# M701D.net
KiCad netlist of a schematic drawn in EAGLE
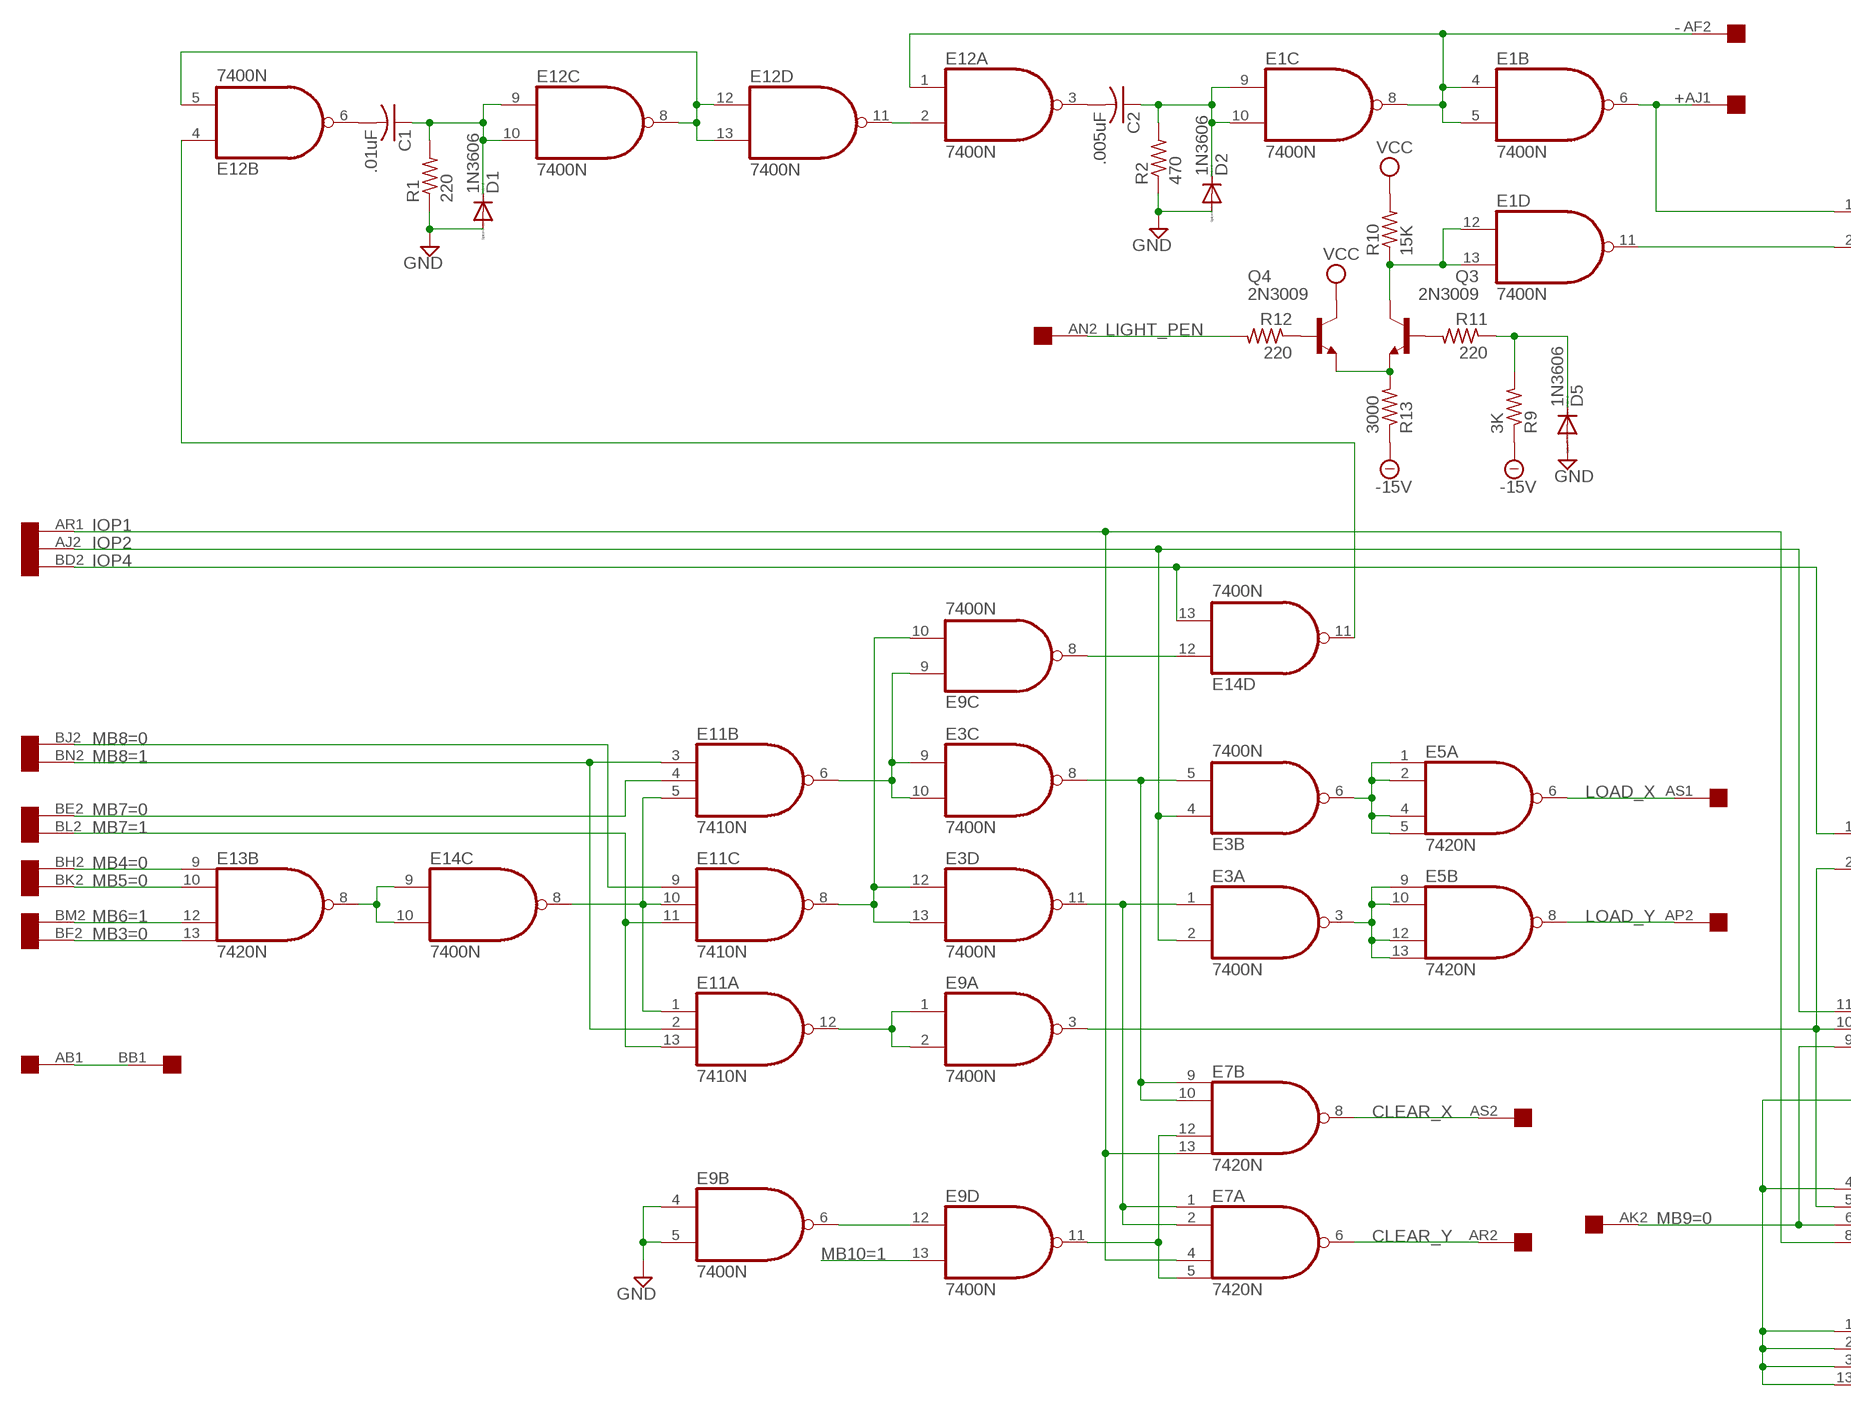
[diagram p0: schematic, sheet 1, part 1 of 2]
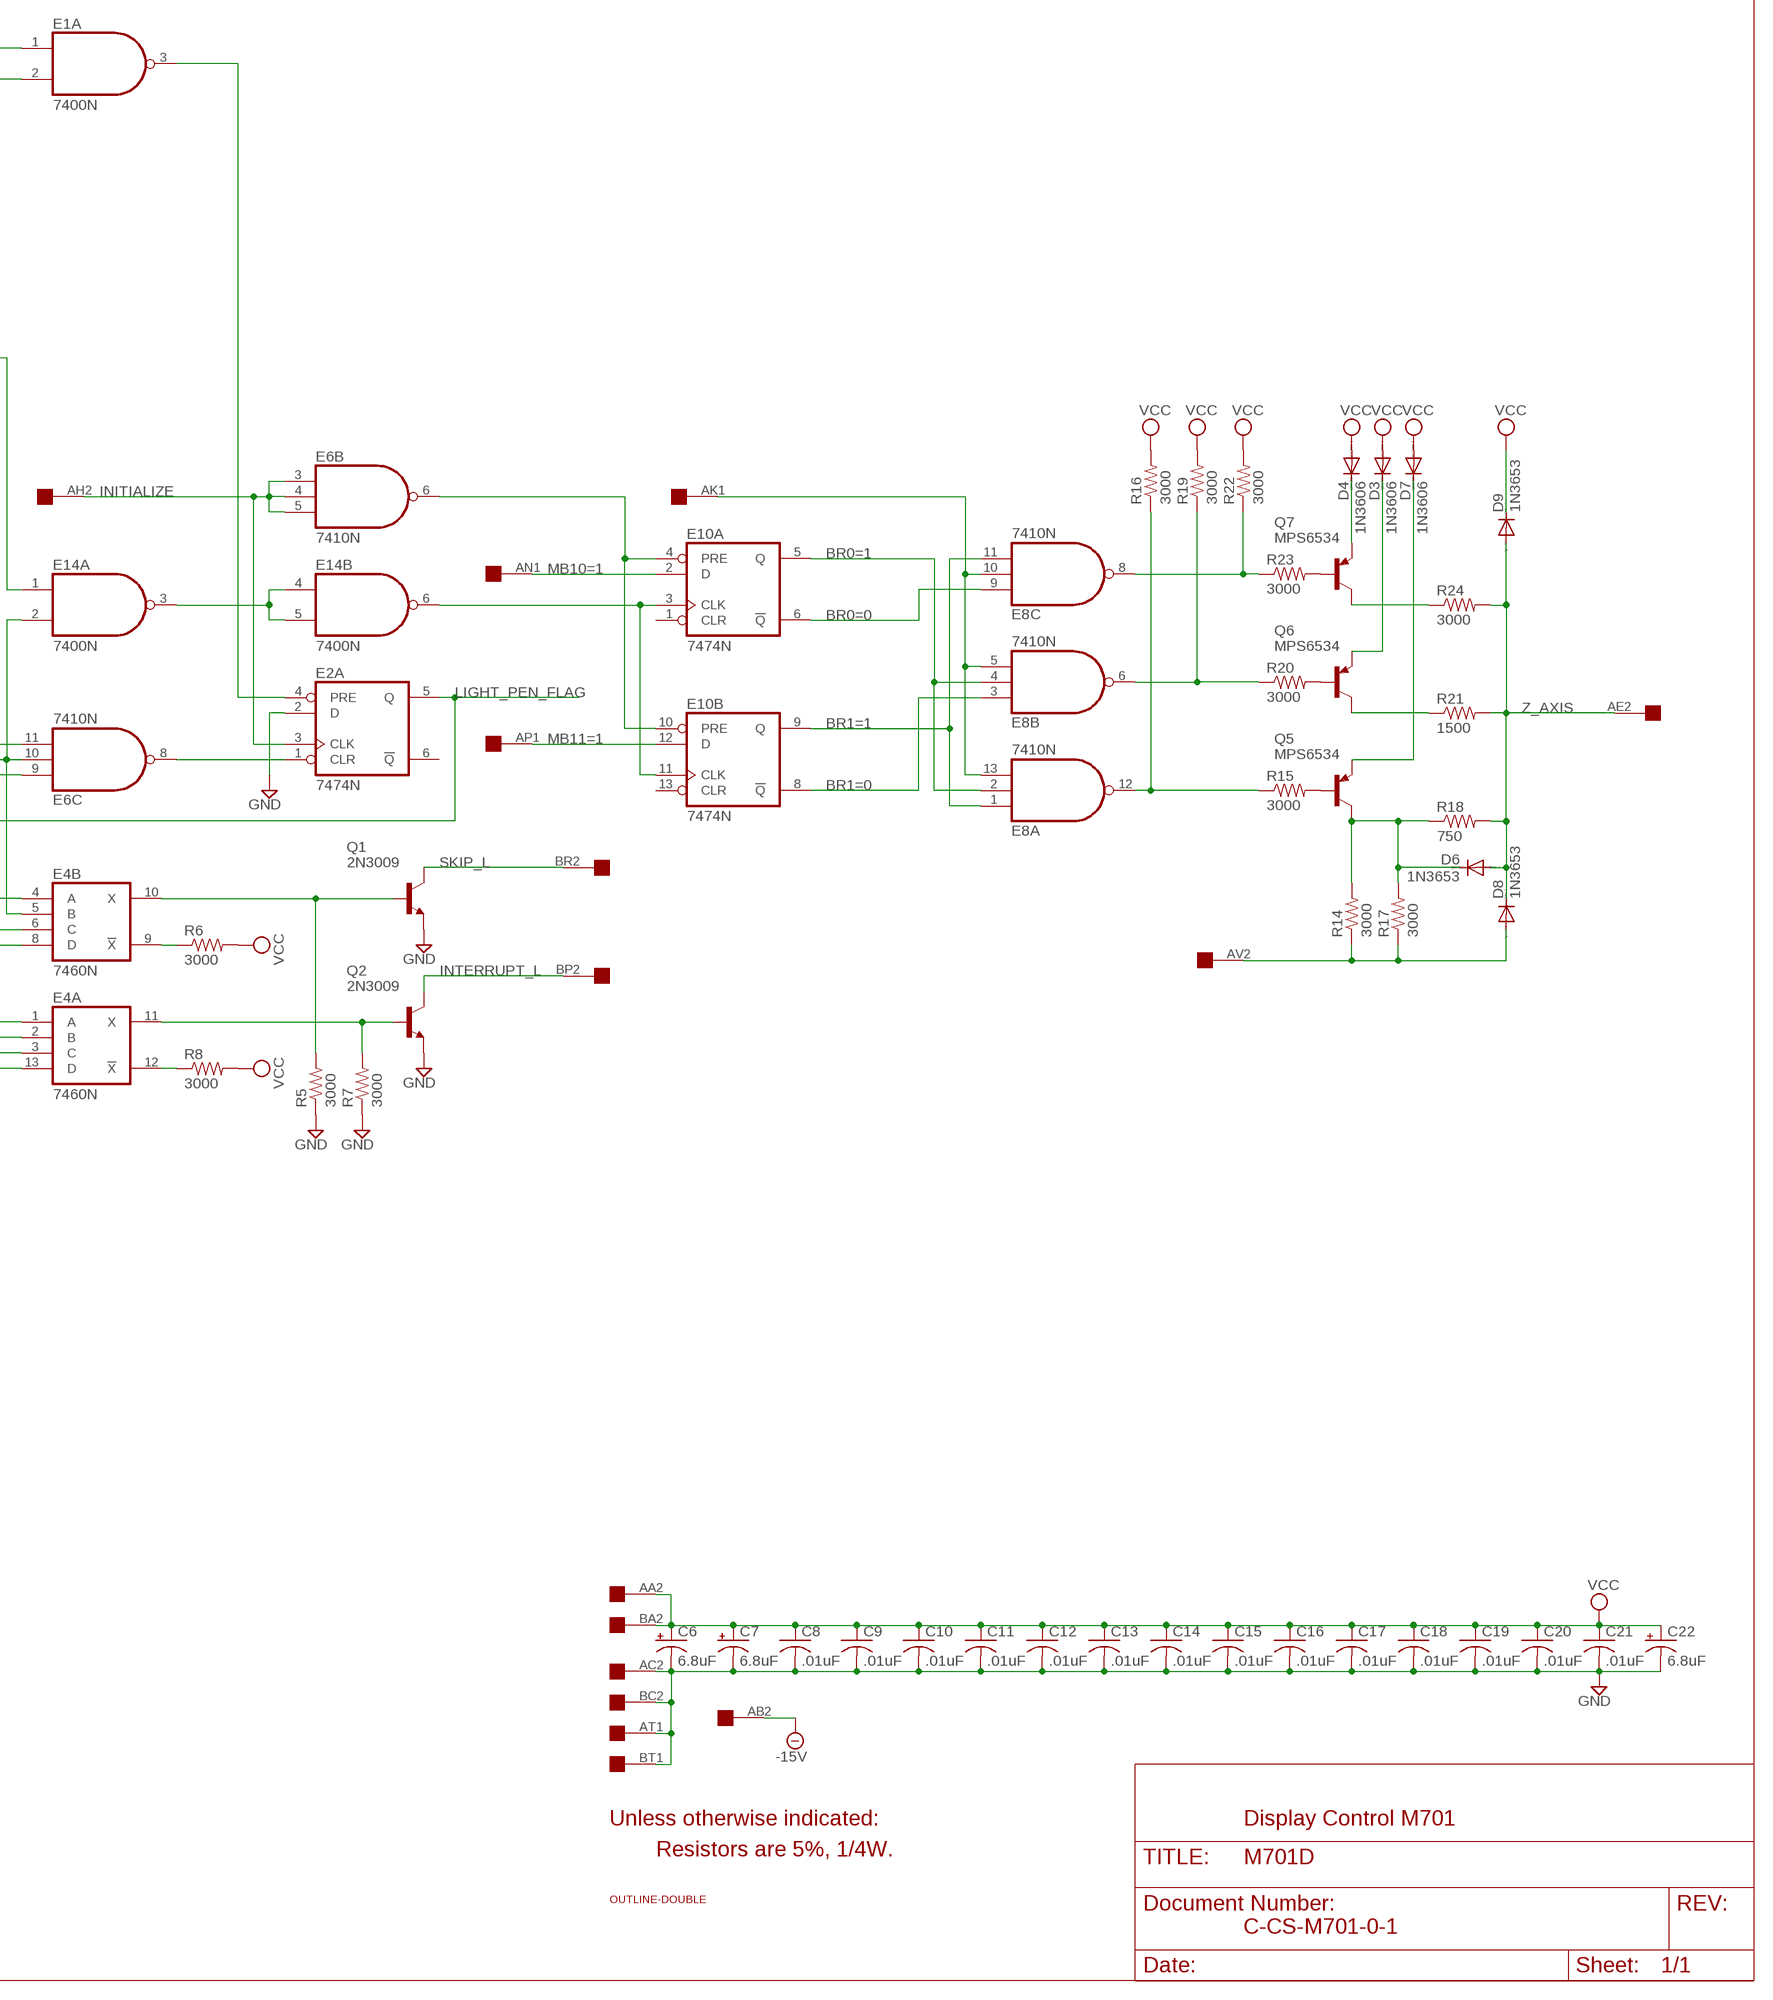
[diagram p1: schematic, sheet 1, part 2 of 2]

(export (version "E")
  (design (tool "Eeschema 10.0.6"))
  (components
    (comp (ref "C1")
      (value ".01uF")
      (footprint "eagle-import:C050-025X075")
      (libsource (lib "eagle-import") (part "C-US050-025X075"))
    )
    (comp (ref "C2")
      (value ".005uF")
      (footprint "eagle-import:C050-025X075")
      (libsource (lib "eagle-import") (part "C-US050-025X075"))
    )
    (comp (ref "C6")
      (value "6.8uF")
      (footprint "eagle-import:E12-8")
      (libsource (lib "eagle-import") (part "CPOL-USE20-8AXIAL"))
    )
    (comp (ref "C7")
      (value "6.8uF")
      (footprint "eagle-import:E12-8")
      (libsource (lib "eagle-import") (part "CPOL-USE20-8AXIAL"))
    )
    (comp (ref "C8")
      (value ".01uF")
      (footprint "eagle-import:C050-025X075")
      (libsource (lib "eagle-import") (part "C-US050-025X075"))
    )
    (comp (ref "C9")
      (value ".01uF")
      (footprint "eagle-import:C050-025X075")
      (libsource (lib "eagle-import") (part "C-US050-025X075"))
    )
    (comp (ref "C10")
      (value ".01uF")
      (footprint "eagle-import:C050-025X075")
      (libsource (lib "eagle-import") (part "C-US050-025X075"))
    )
    (comp (ref "C11")
      (value ".01uF")
      (footprint "eagle-import:C050-025X075")
      (libsource (lib "eagle-import") (part "C-US050-025X075"))
    )
    (comp (ref "C12")
      (value ".01uF")
      (footprint "eagle-import:C050-025X075")
      (libsource (lib "eagle-import") (part "C-US050-025X075"))
    )
    (comp (ref "C13")
      (value ".01uF")
      (footprint "eagle-import:C050-025X075")
      (libsource (lib "eagle-import") (part "C-US050-025X075"))
    )
    (comp (ref "C14")
      (value ".01uF")
      (footprint "eagle-import:C050-025X075")
      (libsource (lib "eagle-import") (part "C-US050-025X075"))
    )
    (comp (ref "C15")
      (value ".01uF")
      (footprint "eagle-import:C050-025X075")
      (libsource (lib "eagle-import") (part "C-US050-025X075"))
    )
    (comp (ref "C16")
      (value ".01uF")
      (footprint "eagle-import:C050-025X075")
      (libsource (lib "eagle-import") (part "C-US050-025X075"))
    )
    (comp (ref "C17")
      (value ".01uF")
      (footprint "eagle-import:C050-025X075")
      (libsource (lib "eagle-import") (part "C-US050-025X075"))
    )
    (comp (ref "C18")
      (value ".01uF")
      (footprint "eagle-import:C050-025X075")
      (libsource (lib "eagle-import") (part "C-US050-025X075"))
    )
    (comp (ref "C19")
      (value ".01uF")
      (footprint "eagle-import:C050-025X075")
      (libsource (lib "eagle-import") (part "C-US050-025X075"))
    )
    (comp (ref "C20")
      (value ".01uF")
      (footprint "eagle-import:C050-025X075")
      (libsource (lib "eagle-import") (part "C-US050-025X075"))
    )
    (comp (ref "C21")
      (value ".01uF")
      (footprint "eagle-import:C050-025X075")
      (libsource (lib "eagle-import") (part "C-US050-025X075"))
    )
    (comp (ref "C22")
      (value "6.8uF")
      (footprint "eagle-import:E12-8")
      (libsource (lib "eagle-import") (part "CPOL-USE20-8AXIAL"))
    )
    (comp (ref "D1")
      (value "1N3606")
      (footprint "eagle-import:DO35-10")
      (libsource (lib "eagle-import") (part "1N4148DO35-10"))
    )
    (comp (ref "D2")
      (value "1N3606")
      (footprint "eagle-import:DO35-10")
      (libsource (lib "eagle-import") (part "1N4148DO35-10"))
    )
    (comp (ref "D3")
      (value "1N3606")
      (footprint "eagle-import:DO35-10")
      (libsource (lib "eagle-import") (part "1N4148DO35-10"))
    )
    (comp (ref "D4")
      (value "1N3606")
      (footprint "eagle-import:DO35-10")
      (libsource (lib "eagle-import") (part "1N4148DO35-10"))
    )
    (comp (ref "D5")
      (value "1N3606")
      (footprint "eagle-import:DO35-10")
      (libsource (lib "eagle-import") (part "1N4148DO35-10"))
    )
    (comp (ref "D6")
      (value "1N3653")
      (footprint "eagle-import:DO35-10")
      (libsource (lib "eagle-import") (part "1N4148DO35-10"))
    )
    (comp (ref "D7")
      (value "1N3606")
      (footprint "eagle-import:DO35-10")
      (libsource (lib "eagle-import") (part "1N4148DO35-10"))
    )
    (comp (ref "D8")
      (value "1N3653")
      (footprint "eagle-import:DO35-10")
      (libsource (lib "eagle-import") (part "1N4148DO35-10"))
    )
    (comp (ref "D9")
      (value "1N3653")
      (footprint "eagle-import:DO35-10")
      (libsource (lib "eagle-import") (part "1N4148DO35-10"))
    )
    (comp (ref "E1")
      (value "7400N")
      (footprint "eagle-import:DIL14")
      (libsource (lib "eagle-import") (part "7400N"))
    )
    (comp (ref "E2")
      (value "7474N")
      (footprint "eagle-import:DIL14")
      (libsource (lib "eagle-import") (part "7474NS"))
    )
    (comp (ref "E3")
      (value "7400N")
      (footprint "eagle-import:DIL14")
      (libsource (lib "eagle-import") (part "7400N"))
    )
    (comp (ref "E4")
      (value "7460N")
      (footprint "eagle-import:DIL14")
      (libsource (lib "eagle-import") (part "7460N"))
    )
    (comp (ref "E5")
      (value "7420N")
      (footprint "eagle-import:DIL14")
      (libsource (lib "eagle-import") (part "7420NS"))
    )
    (comp (ref "E6")
      (value "7410N")
      (footprint "eagle-import:DIL14")
      (libsource (lib "eagle-import") (part "7410N"))
    )
    (comp (ref "E7")
      (value "7420N")
      (footprint "eagle-import:DIL14")
      (libsource (lib "eagle-import") (part "7420NS"))
    )
    (comp (ref "E8")
      (value "7410N")
      (footprint "eagle-import:DIL14")
      (libsource (lib "eagle-import") (part "7410N"))
    )
    (comp (ref "E9")
      (value "7400N")
      (footprint "eagle-import:DIL14")
      (libsource (lib "eagle-import") (part "7400N"))
    )
    (comp (ref "E10")
      (value "7474N")
      (footprint "eagle-import:DIL14")
      (libsource (lib "eagle-import") (part "7474NS"))
    )
    (comp (ref "E11")
      (value "7410N")
      (footprint "eagle-import:DIL14")
      (libsource (lib "eagle-import") (part "7410N"))
    )
    (comp (ref "E12")
      (value "7400N")
      (footprint "eagle-import:DIL14")
      (libsource (lib "eagle-import") (part "7400N"))
    )
    (comp (ref "E13")
      (value "7420N")
      (footprint "eagle-import:DIL14")
      (libsource (lib "eagle-import") (part "7420NS"))
    )
    (comp (ref "E14")
      (value "7400N")
      (footprint "eagle-import:DIL14")
      (libsource (lib "eagle-import") (part "7400N"))
    )
    (comp (ref "Q1")
      (value "2N3009")
      (footprint "eagle-import:TO5")
      (libsource (lib "eagle-import") (part "2N2102"))
    )
    (comp (ref "Q2")
      (value "2N3009")
      (footprint "eagle-import:TO5")
      (libsource (lib "eagle-import") (part "2N2102"))
    )
    (comp (ref "Q3")
      (value "2N3009")
      (footprint "eagle-import:TO5")
      (libsource (lib "eagle-import") (part "2N2102"))
    )
    (comp (ref "Q4")
      (value "2N3009")
      (footprint "eagle-import:TO5")
      (libsource (lib "eagle-import") (part "2N2102"))
    )
    (comp (ref "Q5")
      (value "MPS6534")
      (footprint "eagle-import:TO5")
      (libsource (lib "eagle-import") (part "2N2905"))
    )
    (comp (ref "Q6")
      (value "MPS6534")
      (footprint "eagle-import:TO5")
      (libsource (lib "eagle-import") (part "2N2905"))
    )
    (comp (ref "Q7")
      (value "MPS6534")
      (footprint "eagle-import:TO5")
      (libsource (lib "eagle-import") (part "2N2905"))
    )
    (comp (ref "R1")
      (value "220")
      (footprint "eagle-import:0207_10")
      (libsource (lib "eagle-import") (part "R-US_0207/10"))
    )
    (comp (ref "R2")
      (value "470")
      (footprint "eagle-import:0207_10")
      (libsource (lib "eagle-import") (part "R-US_0207/10"))
    )
    (comp (ref "R5")
      (value "3000")
      (footprint "eagle-import:0207_10")
      (libsource (lib "eagle-import") (part "R-US_0207/10"))
    )
    (comp (ref "R6")
      (value "3000")
      (footprint "eagle-import:0207_10")
      (libsource (lib "eagle-import") (part "R-US_0207/10"))
    )
    (comp (ref "R7")
      (value "3000")
      (footprint "eagle-import:0207_10")
      (libsource (lib "eagle-import") (part "R-US_0207/10"))
    )
    (comp (ref "R8")
      (value "3000")
      (footprint "eagle-import:0207_10")
      (libsource (lib "eagle-import") (part "R-US_0207/10"))
    )
    (comp (ref "R9")
      (value "3K")
      (footprint "eagle-import:0207_10")
      (libsource (lib "eagle-import") (part "R-US_0207/10"))
    )
    (comp (ref "R10")
      (value "15K")
      (footprint "eagle-import:0207_10")
      (libsource (lib "eagle-import") (part "R-US_0207/10"))
    )
    (comp (ref "R11")
      (value "220")
      (footprint "eagle-import:0207_10")
      (libsource (lib "eagle-import") (part "R-US_0207/10"))
    )
    (comp (ref "R12")
      (value "220")
      (footprint "eagle-import:0207_10")
      (libsource (lib "eagle-import") (part "R-US_0207/10"))
    )
    (comp (ref "R13")
      (value "3000")
      (footprint "eagle-import:0207_10")
      (libsource (lib "eagle-import") (part "R-US_0207/10"))
    )
    (comp (ref "R14")
      (value "3000")
      (footprint "eagle-import:0207_10")
      (libsource (lib "eagle-import") (part "R-US_0207/10"))
    )
    (comp (ref "R15")
      (value "3000")
      (footprint "eagle-import:0207_10")
      (libsource (lib "eagle-import") (part "R-US_0207/10"))
    )
    (comp (ref "R16")
      (value "3000")
      (footprint "eagle-import:0207_10")
      (libsource (lib "eagle-import") (part "R-US_0207/10"))
    )
    (comp (ref "R17")
      (value "3000")
      (footprint "eagle-import:0207_10")
      (libsource (lib "eagle-import") (part "R-US_0207/10"))
    )
    (comp (ref "R18")
      (value "750")
      (footprint "eagle-import:0207_10")
      (libsource (lib "eagle-import") (part "R-US_0207/10"))
    )
    (comp (ref "R19")
      (value "3000")
      (footprint "eagle-import:0207_10")
      (libsource (lib "eagle-import") (part "R-US_0207/10"))
    )
    (comp (ref "R20")
      (value "3000")
      (footprint "eagle-import:0207_10")
      (libsource (lib "eagle-import") (part "R-US_0207/10"))
    )
    (comp (ref "R21")
      (value "1500")
      (footprint "eagle-import:0207_10")
      (libsource (lib "eagle-import") (part "R-US_0207/10"))
    )
    (comp (ref "R22")
      (value "3000")
      (footprint "eagle-import:0207_10")
      (libsource (lib "eagle-import") (part "R-US_0207/10"))
    )
    (comp (ref "R23")
      (value "3000")
      (footprint "eagle-import:0207_10")
      (libsource (lib "eagle-import") (part "R-US_0207/10"))
    )
    (comp (ref "R24")
      (value "3000")
      (footprint "eagle-import:0207_10")
      (libsource (lib "eagle-import") (part "R-US_0207/10"))
    )
    (comp (ref "U$1")
      (value "DOUBLE")
      (footprint "eagle-import:EDGE-CON4")
      (libsource (lib "eagle-import") (part "DOUBLE"))
    )
    (comp (ref "U$2")
      (value "OUTLINE-DOUBLE")
      (footprint "eagle-import:DOUBLE")
      (libsource (lib "eagle-import") (part "OUTLINE-DOUBLE"))
    )
  )
  (nets
    (net (code "1") (name "-15V") (class "Default")
      (node (ref "R13") (pin "1") (pinfunction "1_1") (pintype "passive"))
      (node (ref "R9") (pin "1") (pinfunction "1_1") (pintype "passive"))
      (node (ref "U$1") (pin "AB2") (pinfunction "1_AB2") (pintype "bidirectional"))
    )
    (net (code "2") (name "/+") (class "Default")
      (node (ref "E1") (pin "1") (pinfunction "I0_1") (pintype "input"))
      (node (ref "E1") (pin "6") (pinfunction "O_6") (pintype "output"))
      (node (ref "U$1") (pin "AJ1") (pinfunction "1_AJ1") (pintype "bidirectional"))
    )
    (net (code "3") (name "/-") (class "Default")
      (node (ref "E1") (pin "4") (pinfunction "I0_4") (pintype "input"))
      (node (ref "E1") (pin "5") (pinfunction "I1_5") (pintype "input"))
      (node (ref "E1") (pin "8") (pinfunction "O_8") (pintype "output"))
      (node (ref "E12") (pin "1") (pinfunction "I0_1") (pintype "input"))
      (node (ref "U$1") (pin "AF2") (pinfunction "1_AF2") (pintype "bidirectional"))
    )
    (net (code "4") (name "/BR0=0") (class "Default")
      (node (ref "E10") (pin "6") (pinfunction "~{Q}_6") (pintype "output"))
      (node (ref "E8") (pin "9") (pinfunction "I0_9") (pintype "input"))
    )
    (net (code "5") (name "/BR0=1") (class "Default")
      (node (ref "E10") (pin "5") (pinfunction "Q_5") (pintype "output"))
      (node (ref "E8") (pin "2") (pinfunction "I1_2") (pintype "input"))
      (node (ref "E8") (pin "4") (pinfunction "I1_4") (pintype "input"))
    )
    (net (code "6") (name "/BR1=0") (class "Default")
      (node (ref "E10") (pin "8") (pinfunction "~{Q}_8") (pintype "output"))
      (node (ref "E8") (pin "3") (pinfunction "I0_3") (pintype "input"))
    )
    (net (code "7") (name "/BR1=1") (class "Default")
      (node (ref "E10") (pin "9") (pinfunction "Q_9") (pintype "output"))
      (node (ref "E8") (pin "1") (pinfunction "I0_1") (pintype "input"))
      (node (ref "E8") (pin "11") (pinfunction "I2_11") (pintype "input"))
    )
    (net (code "8") (name "/CLEAR_X") (class "Default")
      (node (ref "E7") (pin "8") (pinfunction "O_8") (pintype "output"))
      (node (ref "U$1") (pin "AS2") (pinfunction "1_AS2") (pintype "bidirectional"))
    )
    (net (code "9") (name "/CLEAR_Y") (class "Default")
      (node (ref "E7") (pin "6") (pinfunction "O_6") (pintype "output"))
      (node (ref "U$1") (pin "AR2") (pinfunction "1_AR2") (pintype "bidirectional"))
    )
    (net (code "10") (name "/INITIALIZE") (class "Default")
      (node (ref "E2") (pin "3") (pinfunction "CLK_3") (pintype "input"))
      (node (ref "E6") (pin "3") (pinfunction "I0_3") (pintype "input"))
      (node (ref "E6") (pin "4") (pinfunction "I1_4") (pintype "input"))
      (node (ref "E6") (pin "5") (pinfunction "I2_5") (pintype "input"))
      (node (ref "U$1") (pin "AH2") (pinfunction "1_AH2") (pintype "bidirectional"))
    )
    (net (code "11") (name "/INTERRUPT_L") (class "Default")
      (node (ref "Q2") (pin "3") (pinfunction "C_3") (pintype "passive"))
      (node (ref "U$1") (pin "BP2") (pinfunction "1_BP2") (pintype "bidirectional"))
    )
    (net (code "12") (name "/IOP1") (class "Default")
      (node (ref "E4") (pin "8") (pinfunction "D_8") (pintype "input"))
      (node (ref "E7") (pin "13") (pinfunction "I3_13") (pintype "input"))
      (node (ref "E7") (pin "4") (pinfunction "I2_4") (pintype "input"))
      (node (ref "U$1") (pin "AR1") (pinfunction "1_AR1") (pintype "bidirectional"))
    )
    (net (code "13") (name "/IOP2") (class "Default")
      (node (ref "E3") (pin "2") (pinfunction "I1_2") (pintype "input"))
      (node (ref "E3") (pin "4") (pinfunction "I0_4") (pintype "input"))
      (node (ref "E6") (pin "11") (pinfunction "I2_11") (pintype "input"))
      (node (ref "U$1") (pin "AJ2") (pinfunction "1_AJ2") (pintype "bidirectional"))
    )
    (net (code "14") (name "/IOP4") (class "Default")
      (node (ref "E14") (pin "1") (pinfunction "I0_1") (pintype "input"))
      (node (ref "E14") (pin "13") (pinfunction "I1_13") (pintype "input"))
      (node (ref "U$1") (pin "BD2") (pinfunction "1_BD2") (pintype "bidirectional"))
    )
    (net (code "15") (name "/LIGHT_PEN") (class "Default")
      (node (ref "R12") (pin "2") (pinfunction "2_2") (pintype "passive"))
      (node (ref "U$1") (pin "AN2") (pinfunction "1_AN2") (pintype "bidirectional"))
    )
    (net (code "16") (name "/LIGHT_PEN_FLAG") (class "Default")
      (node (ref "E2") (pin "5") (pinfunction "Q_5") (pintype "output"))
      (node (ref "E4") (pin "1") (pinfunction "A_1") (pintype "input"))
      (node (ref "E4") (pin "13") (pinfunction "D_13") (pintype "input"))
      (node (ref "E4") (pin "2") (pinfunction "B_2") (pintype "input"))
      (node (ref "E4") (pin "3") (pinfunction "C_3") (pintype "input"))
      (node (ref "E4") (pin "4") (pinfunction "A_4") (pintype "input"))
    )
    (net (code "17") (name "/LOAD_X") (class "Default")
      (node (ref "E5") (pin "6") (pinfunction "O_6") (pintype "output"))
      (node (ref "U$1") (pin "AS1") (pinfunction "1_AS1") (pintype "bidirectional"))
    )
    (net (code "18") (name "/LOAD_Y") (class "Default")
      (node (ref "E5") (pin "8") (pinfunction "O_8") (pintype "output"))
      (node (ref "U$1") (pin "AP2") (pinfunction "1_AP2") (pintype "bidirectional"))
    )
    (net (code "19") (name "/MB3=0") (class "Default")
      (node (ref "E13") (pin "13") (pinfunction "I3_13") (pintype "input"))
      (node (ref "U$1") (pin "BF2") (pinfunction "1_BF2") (pintype "bidirectional"))
    )
    (net (code "20") (name "/MB4=0") (class "Default")
      (node (ref "E13") (pin "9") (pinfunction "I0_9") (pintype "input"))
      (node (ref "U$1") (pin "BH2") (pinfunction "1_BH2") (pintype "bidirectional"))
    )
    (net (code "21") (name "/MB5=0") (class "Default")
      (node (ref "E13") (pin "10") (pinfunction "I1_10") (pintype "input"))
      (node (ref "U$1") (pin "BK2") (pinfunction "1_BK2") (pintype "bidirectional"))
    )
    (net (code "22") (name "/MB6=1") (class "Default")
      (node (ref "E13") (pin "12") (pinfunction "I2_12") (pintype "input"))
      (node (ref "U$1") (pin "BM2") (pinfunction "1_BM2") (pintype "bidirectional"))
    )
    (net (code "23") (name "/MB7=0") (class "Default")
      (node (ref "E11") (pin "4") (pinfunction "I1_4") (pintype "input"))
      (node (ref "U$1") (pin "BE2") (pinfunction "1_BE2") (pintype "bidirectional"))
    )
    (net (code "24") (name "/MB7=1") (class "Default")
      (node (ref "E11") (pin "11") (pinfunction "I2_11") (pintype "input"))
      (node (ref "E11") (pin "13") (pinfunction "I2_13") (pintype "input"))
      (node (ref "U$1") (pin "BL2") (pinfunction "1_BL2") (pintype "bidirectional"))
    )
    (net (code "25") (name "/MB8=0") (class "Default")
      (node (ref "E11") (pin "9") (pinfunction "I0_9") (pintype "input"))
      (node (ref "U$1") (pin "BJ2") (pinfunction "1_BJ2") (pintype "bidirectional"))
    )
    (net (code "26") (name "/MB8=1") (class "Default")
      (node (ref "E11") (pin "2") (pinfunction "I1_2") (pintype "input"))
      (node (ref "E11") (pin "3") (pinfunction "I0_3") (pintype "input"))
      (node (ref "U$1") (pin "BN2") (pinfunction "1_BN2") (pintype "bidirectional"))
    )
    (net (code "27") (name "/MB9=0") (class "Default")
      (node (ref "E4") (pin "6") (pinfunction "C_6") (pintype "input"))
      (node (ref "E6") (pin "9") (pinfunction "I0_9") (pintype "input"))
      (node (ref "U$1") (pin "AK2") (pinfunction "1_AK2") (pintype "bidirectional"))
    )
    (net (code "28") (name "/MB10=1") (class "Default")
      (node (ref "E10") (pin "2") (pinfunction "D_2") (pintype "input"))
      (node (ref "E9") (pin "13") (pinfunction "I1_13") (pintype "input"))
      (node (ref "U$1") (pin "AN1") (pinfunction "1_AN1") (pintype "bidirectional"))
    )
    (net (code "29") (name "/MB11=1") (class "Default")
      (node (ref "E10") (pin "12") (pinfunction "D_12") (pintype "input"))
      (node (ref "U$1") (pin "AP1") (pinfunction "1_AP1") (pintype "bidirectional"))
    )
    (net (code "30") (name "/SKIP_L") (class "Default")
      (node (ref "Q1") (pin "3") (pinfunction "C_3") (pintype "passive"))
      (node (ref "U$1") (pin "BR2") (pinfunction "1_BR2") (pintype "bidirectional"))
    )
    (net (code "31") (name "/Z_AXIS") (class "Default")
      (node (ref "D6") (pin "A") (pinfunction "A_A") (pintype "passive"))
      (node (ref "D8") (pin "C") (pinfunction "C_C") (pintype "passive"))
      (node (ref "D9") (pin "A") (pinfunction "A_A") (pintype "passive"))
      (node (ref "R18") (pin "2") (pinfunction "2_2") (pintype "passive"))
      (node (ref "R21") (pin "2") (pinfunction "2_2") (pintype "passive"))
      (node (ref "R24") (pin "2") (pinfunction "2_2") (pintype "passive"))
      (node (ref "U$1") (pin "AE2") (pinfunction "1_AE2") (pintype "bidirectional"))
    )
    (net (code "32") (name "GND") (class "Default")
      (node (ref "C10") (pin "2") (pinfunction "2_2") (pintype "passive"))
      (node (ref "C11") (pin "2") (pinfunction "2_2") (pintype "passive"))
      (node (ref "C12") (pin "2") (pinfunction "2_2") (pintype "passive"))
      (node (ref "C13") (pin "2") (pinfunction "2_2") (pintype "passive"))
      (node (ref "C14") (pin "2") (pinfunction "2_2") (pintype "passive"))
      (node (ref "C15") (pin "2") (pinfunction "2_2") (pintype "passive"))
      (node (ref "C16") (pin "2") (pinfunction "2_2") (pintype "passive"))
      (node (ref "C17") (pin "2") (pinfunction "2_2") (pintype "passive"))
      (node (ref "C18") (pin "2") (pinfunction "2_2") (pintype "passive"))
      (node (ref "C19") (pin "2") (pinfunction "2_2") (pintype "passive"))
      (node (ref "C20") (pin "2") (pinfunction "2_2") (pintype "passive"))
      (node (ref "C21") (pin "2") (pinfunction "2_2") (pintype "passive"))
      (node (ref "C22") (pin "-") (pinfunction "-_-") (pintype "passive"))
      (node (ref "C6") (pin "-") (pinfunction "-_-") (pintype "passive"))
      (node (ref "C7") (pin "-") (pinfunction "-_-") (pintype "passive"))
      (node (ref "C8") (pin "2") (pinfunction "2_2") (pintype "passive"))
      (node (ref "C9") (pin "2") (pinfunction "2_2") (pintype "passive"))
      (node (ref "D1") (pin "A") (pinfunction "A_A") (pintype "passive"))
      (node (ref "D2") (pin "A") (pinfunction "A_A") (pintype "passive"))
      (node (ref "D5") (pin "A") (pinfunction "A_A") (pintype "passive"))
      (node (ref "E2") (pin "2") (pinfunction "D_2") (pintype "input"))
      (node (ref "E9") (pin "4") (pinfunction "I0_4") (pintype "input"))
      (node (ref "E9") (pin "5") (pinfunction "I1_5") (pintype "input"))
      (node (ref "Q1") (pin "1") (pinfunction "E_1") (pintype "passive"))
      (node (ref "Q2") (pin "1") (pinfunction "E_1") (pintype "passive"))
      (node (ref "R1") (pin "1") (pinfunction "1_1") (pintype "passive"))
      (node (ref "R2") (pin "1") (pinfunction "1_1") (pintype "passive"))
      (node (ref "R5") (pin "1") (pinfunction "1_1") (pintype "passive"))
      (node (ref "R7") (pin "1") (pinfunction "1_1") (pintype "passive"))
      (node (ref "U$1") (pin "AC2") (pinfunction "1_AC2") (pintype "bidirectional"))
      (node (ref "U$1") (pin "AT1") (pinfunction "1_AT1") (pintype "bidirectional"))
      (node (ref "U$1") (pin "BC2") (pinfunction "1_BC2") (pintype "bidirectional"))
      (node (ref "U$1") (pin "BT1") (pinfunction "1_BT1") (pintype "bidirectional"))
    )
    (net (code "33") (name "Net-(D5-PadC)") (class "Default")
      (node (ref "D5") (pin "C") (pinfunction "C_C") (pintype "passive"))
      (node (ref "R11") (pin "1") (pinfunction "1_1") (pintype "passive"))
      (node (ref "R9") (pin "2") (pinfunction "2_2") (pintype "passive"))
    )
    (net (code "34") (name "Net-(E1A-I1)") (class "Default")
      (node (ref "E1") (pin "11") (pinfunction "O_11") (pintype "output"))
      (node (ref "E1") (pin "2") (pinfunction "I1_2") (pintype "input"))
    )
    (net (code "35") (name "Net-(E1A-O)") (class "Default")
      (node (ref "E1") (pin "3") (pinfunction "O_3") (pintype "output"))
      (node (ref "E2") (pin "4") (pinfunction "PRE_4") (pintype "input"))
    )
    (net (code "36") (name "Net-(E1C-I0)") (class "Default")
      (node (ref "C2") (pin "1") (pinfunction "1_1") (pintype "passive"))
      (node (ref "D2") (pin "C") (pinfunction "C_C") (pintype "passive"))
      (node (ref "E1") (pin "10") (pinfunction "I1_10") (pintype "input"))
      (node (ref "E1") (pin "9") (pinfunction "I0_9") (pintype "input"))
      (node (ref "R2") (pin "2") (pinfunction "2_2") (pintype "passive"))
    )
    (net (code "37") (name "Net-(E1D-I0)") (class "Default")
      (node (ref "E1") (pin "12") (pinfunction "I0_12") (pintype "input"))
      (node (ref "E1") (pin "13") (pinfunction "I1_13") (pintype "input"))
      (node (ref "Q3") (pin "3") (pinfunction "C_3") (pintype "passive"))
      (node (ref "R10") (pin "1") (pinfunction "1_1") (pintype "passive"))
    )
    (net (code "38") (name "Net-(E2A-CLR)") (class "Default")
      (node (ref "E2") (pin "1") (pinfunction "CLR_1") (pintype "input"))
      (node (ref "E6") (pin "8") (pinfunction "O_8") (pintype "output"))
    )
    (net (code "39") (name "Net-(E3A-I0)") (class "Default")
      (node (ref "E3") (pin "1") (pinfunction "I0_1") (pintype "input"))
      (node (ref "E3") (pin "11") (pinfunction "O_11") (pintype "output"))
      (node (ref "E7") (pin "1") (pinfunction "I0_1") (pintype "input"))
      (node (ref "E7") (pin "2") (pinfunction "I1_2") (pintype "input"))
    )
    (net (code "40") (name "Net-(E3A-O)") (class "Default")
      (node (ref "E3") (pin "3") (pinfunction "O_3") (pintype "output"))
      (node (ref "E5") (pin "10") (pinfunction "I1_10") (pintype "input"))
      (node (ref "E5") (pin "12") (pinfunction "I2_12") (pintype "input"))
      (node (ref "E5") (pin "13") (pinfunction "I3_13") (pintype "input"))
      (node (ref "E5") (pin "9") (pinfunction "I0_9") (pintype "input"))
    )
    (net (code "41") (name "Net-(E3B-I1)") (class "Default")
      (node (ref "E3") (pin "5") (pinfunction "I1_5") (pintype "input"))
      (node (ref "E3") (pin "8") (pinfunction "O_8") (pintype "output"))
      (node (ref "E7") (pin "10") (pinfunction "I1_10") (pintype "input"))
      (node (ref "E7") (pin "9") (pinfunction "I0_9") (pintype "input"))
    )
    (net (code "42") (name "Net-(E3B-O)") (class "Default")
      (node (ref "E3") (pin "6") (pinfunction "O_6") (pintype "output"))
      (node (ref "E5") (pin "1") (pinfunction "I0_1") (pintype "input"))
      (node (ref "E5") (pin "2") (pinfunction "I1_2") (pintype "input"))
      (node (ref "E5") (pin "4") (pinfunction "I2_4") (pintype "input"))
      (node (ref "E5") (pin "5") (pinfunction "I3_5") (pintype "input"))
    )
    (net (code "43") (name "Net-(E4A-X)") (class "Default")
      (node (ref "E4") (pin "11") (pinfunction "X_11") (pintype "output"))
      (node (ref "Q2") (pin "2") (pinfunction "B_2") (pintype "passive"))
      (node (ref "R7") (pin "2") (pinfunction "2_2") (pintype "passive"))
    )
    (net (code "44") (name "Net-(E4A-~{X})") (class "Default")
      (node (ref "E4") (pin "12") (pinfunction "~{X}_12") (pintype "output"))
      (node (ref "R8") (pin "1") (pinfunction "1_1") (pintype "passive"))
    )
    (net (code "45") (name "Net-(E4B-X)") (class "Default")
      (node (ref "E4") (pin "10") (pinfunction "X_10") (pintype "output"))
      (node (ref "Q1") (pin "2") (pinfunction "B_2") (pintype "passive"))
      (node (ref "R5") (pin "2") (pinfunction "2_2") (pintype "passive"))
    )
    (net (code "46") (name "Net-(E4B-~{X})") (class "Default")
      (node (ref "E4") (pin "9") (pinfunction "~{X}_9") (pintype "output"))
      (node (ref "R6") (pin "1") (pinfunction "1_1") (pintype "passive"))
    )
    (net (code "47") (name "Net-(E7A-I3)") (class "Default")
      (node (ref "E7") (pin "12") (pinfunction "I2_12") (pintype "input"))
      (node (ref "E7") (pin "5") (pinfunction "I3_5") (pintype "input"))
      (node (ref "E9") (pin "11") (pinfunction "O_11") (pintype "output"))
    )
    (net (code "48") (name "Net-(E8A-I2)") (class "Default")
      (node (ref "E8") (pin "10") (pinfunction "I1_10") (pintype "input"))
      (node (ref "E8") (pin "13") (pinfunction "I2_13") (pintype "input"))
      (node (ref "E8") (pin "5") (pinfunction "I2_5") (pintype "input"))
      (node (ref "U$1") (pin "AK1") (pinfunction "1_AK1") (pintype "bidirectional"))
    )
    (net (code "49") (name "Net-(E8A-O)") (class "Default")
      (node (ref "E8") (pin "12") (pinfunction "O_12") (pintype "output"))
      (node (ref "R15") (pin "1") (pinfunction "1_1") (pintype "passive"))
      (node (ref "R16") (pin "1") (pinfunction "1_1") (pintype "passive"))
    )
    (net (code "50") (name "Net-(E8B-O)") (class "Default")
      (node (ref "E8") (pin "6") (pinfunction "O_6") (pintype "output"))
      (node (ref "R19") (pin "1") (pinfunction "1_1") (pintype "passive"))
      (node (ref "R20") (pin "1") (pinfunction "1_1") (pintype "passive"))
    )
    (net (code "51") (name "Net-(E8C-O)") (class "Default")
      (node (ref "E8") (pin "8") (pinfunction "O_8") (pintype "output"))
      (node (ref "R22") (pin "1") (pinfunction "1_1") (pintype "passive"))
      (node (ref "R23") (pin "1") (pinfunction "1_1") (pintype "passive"))
    )
    (net (code "52") (name "Net-(E9B-O)") (class "Default")
      (node (ref "E9") (pin "12") (pinfunction "I0_12") (pintype "input"))
      (node (ref "E9") (pin "6") (pinfunction "O_6") (pintype "output"))
    )
    (net (code "53") (name "Net-(E10A-CLK)") (class "Default")
      (node (ref "E10") (pin "11") (pinfunction "CLK_11") (pintype "input"))
      (node (ref "E10") (pin "3") (pinfunction "CLK_3") (pintype "input"))
      (node (ref "E14") (pin "6") (pinfunction "O_6") (pintype "output"))
    )
    (net (code "54") (name "Net-(E10A-PRE)") (class "Default")
      (node (ref "E10") (pin "10") (pinfunction "PRE_10") (pintype "input"))
      (node (ref "E10") (pin "4") (pinfunction "PRE_4") (pintype "input"))
      (node (ref "E6") (pin "6") (pinfunction "O_6") (pintype "output"))
    )
    (net (code "55") (name "Net-(E11A-I0)") (class "Default")
      (node (ref "E11") (pin "1") (pinfunction "I0_1") (pintype "input"))
      (node (ref "E11") (pin "10") (pinfunction "I1_10") (pintype "input"))
      (node (ref "E11") (pin "5") (pinfunction "I2_5") (pintype "input"))
      (node (ref "E14") (pin "8") (pinfunction "O_8") (pintype "output"))
    )
    (net (code "56") (name "Net-(E11A-O)") (class "Default")
      (node (ref "E11") (pin "12") (pinfunction "O_12") (pintype "output"))
      (node (ref "E9") (pin "1") (pinfunction "I0_1") (pintype "input"))
      (node (ref "E9") (pin "2") (pinfunction "I1_2") (pintype "input"))
    )
    (net (code "57") (name "Net-(E11B-O)") (class "Default")
      (node (ref "E11") (pin "6") (pinfunction "O_6") (pintype "output"))
      (node (ref "E3") (pin "10") (pinfunction "I1_10") (pintype "input"))
      (node (ref "E3") (pin "9") (pinfunction "I0_9") (pintype "input"))
      (node (ref "E9") (pin "9") (pinfunction "I0_9") (pintype "input"))
    )
    (net (code "58") (name "Net-(E11C-O)") (class "Default")
      (node (ref "E11") (pin "8") (pinfunction "O_8") (pintype "output"))
      (node (ref "E3") (pin "12") (pinfunction "I0_12") (pintype "input"))
      (node (ref "E3") (pin "13") (pinfunction "I1_13") (pintype "input"))
      (node (ref "E9") (pin "10") (pinfunction "I1_10") (pintype "input"))
    )
    (net (code "59") (name "Net-(E12A-I1)") (class "Default")
      (node (ref "E12") (pin "11") (pinfunction "O_11") (pintype "output"))
      (node (ref "E12") (pin "2") (pinfunction "I1_2") (pintype "input"))
    )
    (net (code "60") (name "Net-(E12A-O)") (class "Default")
      (node (ref "C2") (pin "2") (pinfunction "2_2") (pintype "passive"))
      (node (ref "E12") (pin "3") (pinfunction "O_3") (pintype "output"))
    )
    (net (code "61") (name "Net-(E12B-I0)") (class "Default")
      (node (ref "E12") (pin "4") (pinfunction "I0_4") (pintype "input"))
      (node (ref "E14") (pin "11") (pinfunction "O_11") (pintype "output"))
    )
    (net (code "62") (name "Net-(E12B-I1)") (class "Default")
      (node (ref "E12") (pin "12") (pinfunction "I0_12") (pintype "input"))
      (node (ref "E12") (pin "13") (pinfunction "I1_13") (pintype "input"))
      (node (ref "E12") (pin "5") (pinfunction "I1_5") (pintype "input"))
      (node (ref "E12") (pin "8") (pinfunction "O_8") (pintype "output"))
    )
    (net (code "63") (name "Net-(E12B-O)") (class "Default")
      (node (ref "C1") (pin "2") (pinfunction "2_2") (pintype "passive"))
      (node (ref "E12") (pin "6") (pinfunction "O_6") (pintype "output"))
    )
    (net (code "64") (name "Net-(E12C-I0)") (class "Default")
      (node (ref "C1") (pin "1") (pinfunction "1_1") (pintype "passive"))
      (node (ref "D1") (pin "C") (pinfunction "C_C") (pintype "passive"))
      (node (ref "E12") (pin "10") (pinfunction "I1_10") (pintype "input"))
      (node (ref "E12") (pin "9") (pinfunction "I0_9") (pintype "input"))
      (node (ref "R1") (pin "2") (pinfunction "2_2") (pintype "passive"))
    )
    (net (code "65") (name "Net-(E13B-O)") (class "Default")
      (node (ref "E13") (pin "8") (pinfunction "O_8") (pintype "output"))
      (node (ref "E14") (pin "10") (pinfunction "I1_10") (pintype "input"))
      (node (ref "E14") (pin "9") (pinfunction "I0_9") (pintype "input"))
    )
    (net (code "66") (name "Net-(E14A-I1)") (class "Default")
      (node (ref "E14") (pin "2") (pinfunction "I1_2") (pintype "input"))
      (node (ref "E4") (pin "5") (pinfunction "B_5") (pintype "input"))
      (node (ref "E6") (pin "10") (pinfunction "I1_10") (pintype "input"))
      (node (ref "E9") (pin "3") (pinfunction "O_3") (pintype "output"))
    )
    (net (code "67") (name "Net-(E14A-O)") (class "Default")
      (node (ref "E14") (pin "3") (pinfunction "O_3") (pintype "output"))
      (node (ref "E14") (pin "4") (pinfunction "I0_4") (pintype "input"))
      (node (ref "E14") (pin "5") (pinfunction "I1_5") (pintype "input"))
    )
    (net (code "68") (name "Net-(E14D-I0)") (class "Default")
      (node (ref "E14") (pin "12") (pinfunction "I0_12") (pintype "input"))
      (node (ref "E9") (pin "8") (pinfunction "O_8") (pintype "output"))
    )
    (net (code "69") (name "Net-(Q3-B)") (class "Default")
      (node (ref "Q3") (pin "2") (pinfunction "B_2") (pintype "passive"))
      (node (ref "R11") (pin "2") (pinfunction "2_2") (pintype "passive"))
    )
    (net (code "70") (name "Net-(Q3-E)") (class "Default")
      (node (ref "Q3") (pin "1") (pinfunction "E_1") (pintype "passive"))
      (node (ref "Q4") (pin "1") (pinfunction "E_1") (pintype "passive"))
      (node (ref "R13") (pin "2") (pinfunction "2_2") (pintype "passive"))
    )
    (net (code "71") (name "Net-(Q4-B)") (class "Default")
      (node (ref "Q4") (pin "2") (pinfunction "B_2") (pintype "passive"))
      (node (ref "R12") (pin "1") (pinfunction "1_1") (pintype "passive"))
    )
    (net (code "72") (name "Net-(Q5-B)") (class "Default")
      (node (ref "Q5") (pin "2") (pinfunction "B_2") (pintype "passive"))
      (node (ref "R15") (pin "2") (pinfunction "2_2") (pintype "passive"))
    )
    (net (code "73") (name "Net-(Q5-C)") (class "Default")
      (node (ref "D6") (pin "C") (pinfunction "C_C") (pintype "passive"))
      (node (ref "Q5") (pin "3") (pinfunction "C_3") (pintype "passive"))
      (node (ref "R14") (pin "2") (pinfunction "2_2") (pintype "passive"))
      (node (ref "R17") (pin "2") (pinfunction "2_2") (pintype "passive"))
      (node (ref "R18") (pin "1") (pinfunction "1_1") (pintype "passive"))
    )
    (net (code "74") (name "Net-(Q5-E)") (class "Default")
      (node (ref "D7") (pin "C") (pinfunction "C_C") (pintype "passive"))
      (node (ref "Q5") (pin "1") (pinfunction "E_1") (pintype "passive"))
    )
    (net (code "75") (name "Net-(Q6-B)") (class "Default")
      (node (ref "Q6") (pin "2") (pinfunction "B_2") (pintype "passive"))
      (node (ref "R20") (pin "2") (pinfunction "2_2") (pintype "passive"))
    )
    (net (code "76") (name "Net-(Q6-C)") (class "Default")
      (node (ref "Q6") (pin "3") (pinfunction "C_3") (pintype "passive"))
      (node (ref "R21") (pin "1") (pinfunction "1_1") (pintype "passive"))
    )
    (net (code "77") (name "Net-(Q6-E)") (class "Default")
      (node (ref "D3") (pin "C") (pinfunction "C_C") (pintype "passive"))
      (node (ref "Q6") (pin "1") (pinfunction "E_1") (pintype "passive"))
    )
    (net (code "78") (name "Net-(Q7-B)") (class "Default")
      (node (ref "Q7") (pin "2") (pinfunction "B_2") (pintype "passive"))
      (node (ref "R23") (pin "2") (pinfunction "2_2") (pintype "passive"))
    )
    (net (code "79") (name "Net-(Q7-C)") (class "Default")
      (node (ref "Q7") (pin "3") (pinfunction "C_3") (pintype "passive"))
      (node (ref "R24") (pin "1") (pinfunction "1_1") (pintype "passive"))
    )
    (net (code "80") (name "Net-(Q7-E)") (class "Default")
      (node (ref "D4") (pin "C") (pinfunction "C_C") (pintype "passive"))
      (node (ref "Q7") (pin "1") (pinfunction "E_1") (pintype "passive"))
    )
    (net (code "81") (name "Net-(U$1AJ-1)") (class "Default")
      (node (ref "D8") (pin "A") (pinfunction "A_A") (pintype "passive"))
      (node (ref "R14") (pin "1") (pinfunction "1_1") (pintype "passive"))
      (node (ref "R17") (pin "1") (pinfunction "1_1") (pintype "passive"))
      (node (ref "U$1") (pin "AV2") (pinfunction "1_AV2") (pintype "bidirectional"))
    )
    (net (code "82") (name "Net-(U$1AM-1)") (class "Default")
      (node (ref "U$1") (pin "AB1") (pinfunction "1_AB1") (pintype "bidirectional"))
      (node (ref "U$1") (pin "BB1") (pinfunction "1_BB1") (pintype "bidirectional"))
    )
    (net (code "83") (name "VCC") (class "Default")
      (node (ref "C10") (pin "1") (pinfunction "1_1") (pintype "passive"))
      (node (ref "C11") (pin "1") (pinfunction "1_1") (pintype "passive"))
      (node (ref "C12") (pin "1") (pinfunction "1_1") (pintype "passive"))
      (node (ref "C13") (pin "1") (pinfunction "1_1") (pintype "passive"))
      (node (ref "C14") (pin "1") (pinfunction "1_1") (pintype "passive"))
      (node (ref "C15") (pin "1") (pinfunction "1_1") (pintype "passive"))
      (node (ref "C16") (pin "1") (pinfunction "1_1") (pintype "passive"))
      (node (ref "C17") (pin "1") (pinfunction "1_1") (pintype "passive"))
      (node (ref "C18") (pin "1") (pinfunction "1_1") (pintype "passive"))
      (node (ref "C19") (pin "1") (pinfunction "1_1") (pintype "passive"))
      (node (ref "C20") (pin "1") (pinfunction "1_1") (pintype "passive"))
      (node (ref "C21") (pin "1") (pinfunction "1_1") (pintype "passive"))
      (node (ref "C22") (pin "+") (pinfunction "+_+") (pintype "passive"))
      (node (ref "C6") (pin "+") (pinfunction "+_+") (pintype "passive"))
      (node (ref "C7") (pin "+") (pinfunction "+_+") (pintype "passive"))
      (node (ref "C8") (pin "1") (pinfunction "1_1") (pintype "passive"))
      (node (ref "C9") (pin "1") (pinfunction "1_1") (pintype "passive"))
      (node (ref "D3") (pin "A") (pinfunction "A_A") (pintype "passive"))
      (node (ref "D4") (pin "A") (pinfunction "A_A") (pintype "passive"))
      (node (ref "D7") (pin "A") (pinfunction "A_A") (pintype "passive"))
      (node (ref "D9") (pin "C") (pinfunction "C_C") (pintype "passive"))
      (node (ref "Q4") (pin "3") (pinfunction "C_3") (pintype "passive"))
      (node (ref "R10") (pin "2") (pinfunction "2_2") (pintype "passive"))
      (node (ref "R16") (pin "2") (pinfunction "2_2") (pintype "passive"))
      (node (ref "R19") (pin "2") (pinfunction "2_2") (pintype "passive"))
      (node (ref "R22") (pin "2") (pinfunction "2_2") (pintype "passive"))
      (node (ref "R6") (pin "2") (pinfunction "2_2") (pintype "passive"))
      (node (ref "R8") (pin "2") (pinfunction "2_2") (pintype "passive"))
      (node (ref "U$1") (pin "AA2") (pinfunction "1_AA2") (pintype "bidirectional"))
      (node (ref "U$1") (pin "BA2") (pinfunction "1_BA2") (pintype "bidirectional"))
    )
    (net (code "84") (name "unconnected-(E2A-~{Q}-Pad6)") (class "Default")
      (node (ref "E2") (pin "6") (pinfunction "~{Q}_6") (pintype "output"))
    )
    (net (code "85") (name "unconnected-(E10A-CLR-Pad1)") (class "Default")
      (node (ref "E10") (pin "1") (pinfunction "CLR_1") (pintype "input"))
    )
    (net (code "86") (name "unconnected-(E10B-CLR-Pad13)") (class "Default")
      (node (ref "E10") (pin "13") (pinfunction "CLR_13") (pintype "input"))
    )
  )
)
